# 6301_Lab3_ADC.net
KiCad netlist of a schematic drawn in Altium Designer
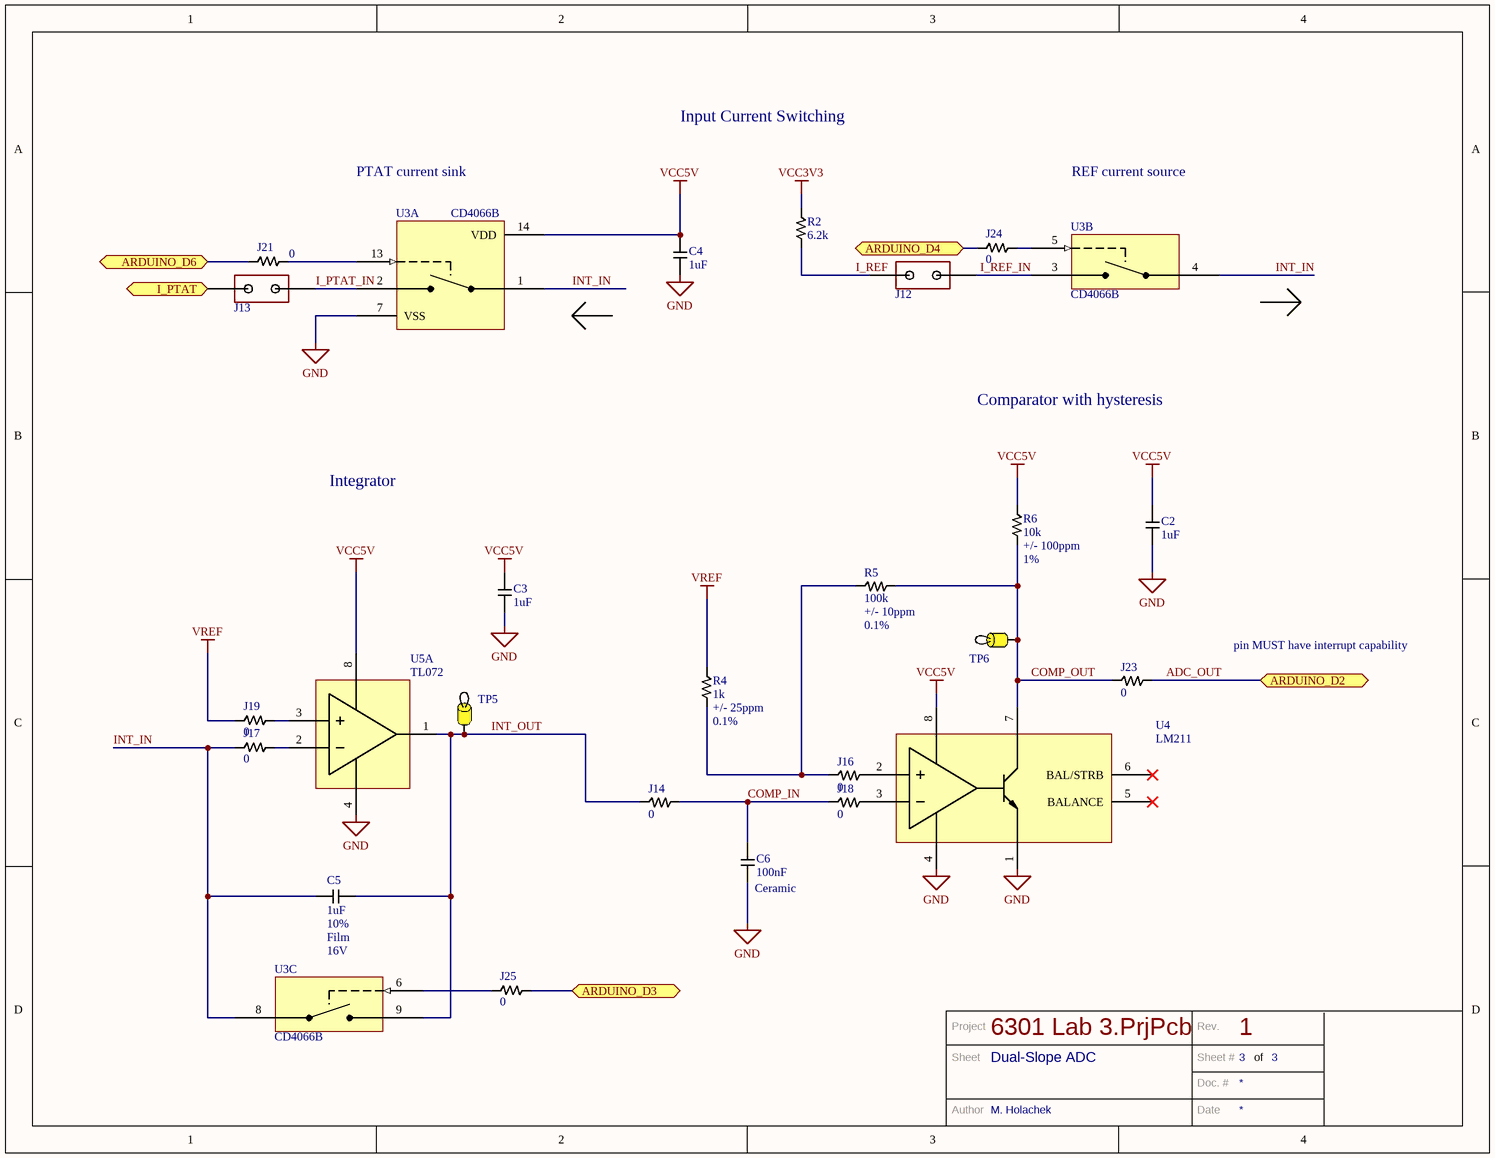
[diagram p0: 6301 Lab3 ADC.SchDoc]

(export (version "E")
  (design (tool "Eeschema 10.0.6"))
  (components
    (comp (ref "C2")
      (value "1uF")
      (footprint "CAP0805")
      (description "Capacitor, 0805 Package")
      (fields (field (name "TOLERANCE") "10%") (field (name "VOLTAGE") "25V"))
      (libsource (lib "6301 Lab 3") (part "Capacitor"))
    )
    (comp (ref "C3")
      (value "1uF")
      (footprint "CAP0805")
      (description "Capacitor, 0805 Package")
      (fields (field (name "TOLERANCE") "10%") (field (name "VOLTAGE") "25V"))
      (libsource (lib "6301 Lab 3") (part "Capacitor"))
    )
    (comp (ref "C4")
      (value "1uF")
      (footprint "CAP0805")
      (description "Capacitor, 0805 Package")
      (fields (field (name "TOLERANCE") "10%") (field (name "VOLTAGE") "25V"))
      (libsource (lib "6301 Lab 3") (part "Capacitor"))
    )
    (comp (ref "C5")
      (value "1uF")
      (footprint "CAP0805")
      (description "Capacitor, 0805 Package")
      (fields (field (name "TOLERANCE") "10%") (field (name "TYPE") "Film") (field (name "VOLTAGE") "16V"))
      (libsource (lib "6301 Lab 3") (part "Capacitor"))
    )
    (comp (ref "C6")
      (value "100nF")
      (footprint "CAP0805")
      (description "Capacitor, 0805 Package")
      (fields (field (name "TOLERANCE") "10%") (field (name "TYPE") "Ceramic") (field (name "VOLTAGE") "50V"))
      (libsource (lib "6301 Lab 3") (part "Capacitor"))
    )
    (comp (ref "J12")
      (value "Jumper")
      (footprint "1X02")
      (description "1x2 2.54mm Jumper")
      (libsource (lib "6301 Lab 3") (part "1x2"))
    )
    (comp (ref "J13")
      (value "Jumper")
      (footprint "1X02")
      (description "1x2 2.54mm Jumper")
      (libsource (lib "6301 Lab 3") (part "1x2"))
    )
    (comp (ref "J14")
      (value "0")
      (footprint "JUMP0402")
      (description "Jumper, 0402 Package")
      (libsource (lib "6301 Lab 3") (part "Jumper 0402"))
    )
    (comp (ref "J16")
      (value "0")
      (footprint "JUMP0402")
      (description "Jumper, 0402 Package")
      (libsource (lib "6301 Lab 3") (part "Jumper 0402"))
    )
    (comp (ref "J17")
      (value "0")
      (footprint "JUMP0402")
      (description "Jumper, 0402 Package")
      (libsource (lib "6301 Lab 3") (part "Jumper 0402"))
    )
    (comp (ref "J18")
      (value "0")
      (footprint "JUMP0402")
      (description "Jumper, 0402 Package")
      (libsource (lib "6301 Lab 3") (part "Jumper 0402"))
    )
    (comp (ref "J19")
      (value "0")
      (footprint "JUMP0402")
      (description "Jumper, 0402 Package")
      (libsource (lib "6301 Lab 3") (part "Jumper 0402"))
    )
    (comp (ref "J21")
      (value "0")
      (footprint "JUMP0402")
      (description "Jumper, 0402 Package")
      (libsource (lib "6301 Lab 3") (part "Jumper 0402"))
    )
    (comp (ref "J23")
      (value "0")
      (footprint "JUMP0402")
      (description "Jumper, 0402 Package")
      (libsource (lib "6301 Lab 3") (part "Jumper 0402"))
    )
    (comp (ref "J24")
      (value "0")
      (footprint "JUMP0402")
      (description "Jumper, 0402 Package")
      (libsource (lib "6301 Lab 3") (part "Jumper 0402"))
    )
    (comp (ref "J25")
      (value "0")
      (footprint "JUMP0402")
      (description "Jumper, 0402 Package")
      (libsource (lib "6301 Lab 3") (part "Jumper 0402"))
    )
    (comp (ref "R2")
      (value "6.2k")
      (footprint "RES0805")
      (description "Resistor, 0805 Package")
      (fields (field (name "TOLERANCE") "0.1%"))
      (libsource (lib "6301 Lab 3") (part "Resistor"))
    )
    (comp (ref "R4")
      (value "1k")
      (footprint "RES0805")
      (description "Resistor, 0805 Package")
      (fields (field (name "TEMP CO") "+/- 25ppm") (field (name "TOLERANCE") "0.1%"))
      (libsource (lib "6301 Lab 3") (part "Resistor"))
    )
    (comp (ref "R5")
      (value "100k")
      (footprint "RES0805")
      (description "Resistor, 0805 Package")
      (fields (field (name "TEMP CO") "+/- 10ppm") (field (name "TOLERANCE") "0.1%"))
      (libsource (lib "6301 Lab 3") (part "Resistor"))
    )
    (comp (ref "R6")
      (value "10k")
      (footprint "RES0805")
      (description "Resistor, 0805 Package")
      (fields (field (name "TEMP CO") "+/- 100ppm") (field (name "TOLERANCE") "1%"))
      (libsource (lib "6301 Lab 3") (part "Resistor"))
    )
    (comp (ref "TP5")
      (value "Yellow")
      (footprint "TP_YELLOW")
      (description "Yellow Test Point")
      (libsource (lib "") (part "Yellow Test Point_1"))
    )
    (comp (ref "TP6")
      (value "Yellow")
      (footprint "TP_YELLOW")
      (description "Yellow Test Point")
      (libsource (lib "6301 Lab 3") (part "Yellow Test Point"))
    )
    (comp (ref "U3")
      (value "CD4066B")
      (footprint "SOIC14")
      (description "CMOS Quad Bilateral Switch")
      (fields (field (name "MANUFACTURER") "Texas Instruments"))
      (libsource (lib "") (part "CD4066B_2"))
    )
    (comp (ref "U4")
      (value "LM211")
      (footprint "SOIC8")
      (description "Single Differential Comparator")
      (fields (field (name "MANUFACTURER") "Texas Instruments"))
      (libsource (lib "6301 Lab 3") (part "LMx11"))
    )
    (comp (ref "U5")
      (value "TL072")
      (footprint "SOIC8")
      (description "Dual Low-Noise JFET-Input Op Amp")
      (libsource (lib "6301 Lab 3") (part "TL07xx"))
    )
  )
  (nets
    (net (code "1") (name "/ADC_OUT") (class "Default")
      (node (ref "J23") (pin "1") (pinfunction "1_1") (pintype "passive"))
    )
    (net (code "2") (name "/ARDUINO_D3") (class "Default")
      (node (ref "J25") (pin "2") (pinfunction "2_2") (pintype "passive"))
    )
    (net (code "3") (name "/ARDUINO_D4") (class "Default")
      (node (ref "J24") (pin "1") (pinfunction "1_1") (pintype "passive"))
    )
    (net (code "4") (name "/ARDUINO_D6") (class "Default")
      (node (ref "J21") (pin "1") (pinfunction "1_1") (pintype "passive"))
    )
    (net (code "5") (name "/COMP_IN") (class "Default")
      (node (ref "C6") (pin "2") (pinfunction "2_2") (pintype "passive"))
      (node (ref "J14") (pin "1") (pinfunction "1_1") (pintype "passive"))
      (node (ref "J18") (pin "2") (pinfunction "2_2") (pintype "passive"))
    )
    (net (code "6") (name "/COMP_OUT") (class "Default")
      (node (ref "J23") (pin "2") (pinfunction "2_2") (pintype "passive"))
      (node (ref "R5") (pin "1") (pinfunction "1_1") (pintype "passive"))
      (node (ref "R6") (pin "1") (pinfunction "1_1") (pintype "passive"))
      (node (ref "TP6") (pin "1") (pinfunction "1_1") (pintype "passive"))
      (node (ref "U4") (pin "7") (pinfunction "COL_OUT_7") (pintype "passive"))
    )
    (net (code "7") (name "/INT_IN") (class "Default")
      (node (ref "C5") (pin "1") (pinfunction "1_1") (pintype "passive"))
      (node (ref "J17") (pin "1") (pinfunction "1_1") (pintype "passive"))
      (node (ref "U3") (pin "1") (pinfunction "IN_A_1") (pintype "passive"))
      (node (ref "U3") (pin "4") (pinfunction "IN_B_4") (pintype "passive"))
      (node (ref "U3") (pin "8") (pinfunction "IN_C_8") (pintype "passive"))
    )
    (net (code "8") (name "/INT_OUT") (class "Default")
      (node (ref "C5") (pin "2") (pinfunction "2_2") (pintype "passive"))
      (node (ref "J14") (pin "2") (pinfunction "2_2") (pintype "passive"))
      (node (ref "TP5") (pin "1") (pinfunction "1_1") (pintype "passive"))
      (node (ref "U3") (pin "9") (pinfunction "OUT_C_9") (pintype "passive"))
      (node (ref "U5") (pin "1") (pinfunction "1OUT_1") (pintype "passive"))
    )
    (net (code "9") (name "/I_PTAT") (class "Default")
      (node (ref "J13") (pin "2") (pinfunction "2_2") (pintype "passive"))
    )
    (net (code "10") (name "/I_PTAT_IN") (class "Default")
      (node (ref "J13") (pin "1") (pinfunction "1_1") (pintype "passive"))
      (node (ref "U3") (pin "2") (pinfunction "OUT_A_2") (pintype "passive"))
    )
    (net (code "11") (name "/I_REF") (class "Default")
      (node (ref "J12") (pin "2") (pinfunction "2_2") (pintype "passive"))
      (node (ref "R2") (pin "1") (pinfunction "1_1") (pintype "passive"))
    )
    (net (code "12") (name "/I_REF_IN") (class "Default")
      (node (ref "J12") (pin "1") (pinfunction "1_1") (pintype "passive"))
      (node (ref "U3") (pin "3") (pinfunction "OUT_B_3") (pintype "passive"))
    )
    (net (code "13") (name "GND") (class "Default")
      (node (ref "C2") (pin "1") (pinfunction "1_1") (pintype "passive"))
      (node (ref "C3") (pin "1") (pinfunction "1_1") (pintype "passive"))
      (node (ref "C4") (pin "1") (pinfunction "1_1") (pintype "passive"))
      (node (ref "C6") (pin "1") (pinfunction "1_1") (pintype "passive"))
      (node (ref "U3") (pin "7") (pinfunction "VSS_7") (pintype "power_in"))
      (node (ref "U4") (pin "1") (pinfunction "EMIT_OUT_1") (pintype "passive"))
      (node (ref "U4") (pin "4") (pinfunction "VCC-_4") (pintype "passive"))
      (node (ref "U5") (pin "4") (pinfunction "VCC-_4") (pintype "passive"))
    )
    (net (code "14") (name "Net-(J16-Pad2)") (class "Default")
      (node (ref "J16") (pin "2") (pinfunction "2_2") (pintype "passive"))
      (node (ref "R4") (pin "1") (pinfunction "1_1") (pintype "passive"))
      (node (ref "R5") (pin "2") (pinfunction "2_2") (pintype "passive"))
    )
    (net (code "15") (name "Net-(U3A-EN_A)") (class "Default")
      (node (ref "J21") (pin "2") (pinfunction "2_2") (pintype "passive"))
      (node (ref "U3") (pin "13") (pinfunction "EN_A_13") (pintype "input"))
    )
    (net (code "16") (name "Net-(U3B-EN_B)") (class "Default")
      (node (ref "J24") (pin "2") (pinfunction "2_2") (pintype "passive"))
      (node (ref "U3") (pin "5") (pinfunction "EN_B_5") (pintype "input"))
    )
    (net (code "17") (name "Net-(U3C-EN_C)") (class "Default")
      (node (ref "J25") (pin "1") (pinfunction "1_1") (pintype "passive"))
      (node (ref "U3") (pin "6") (pinfunction "EN_C_6") (pintype "input"))
    )
    (net (code "18") (name "Net-(U4-IN+)") (class "Default")
      (node (ref "J16") (pin "1") (pinfunction "1_1") (pintype "passive"))
      (node (ref "U4") (pin "2") (pinfunction "IN+_2") (pintype "passive"))
    )
    (net (code "19") (name "Net-(U4-IN-)") (class "Default")
      (node (ref "J18") (pin "1") (pinfunction "1_1") (pintype "passive"))
      (node (ref "U4") (pin "3") (pinfunction "IN-_3") (pintype "passive"))
    )
    (net (code "20") (name "Net-(U5A-1IN+)") (class "Default")
      (node (ref "J19") (pin "2") (pinfunction "2_2") (pintype "passive"))
      (node (ref "U5") (pin "3") (pinfunction "1IN+_3") (pintype "passive"))
    )
    (net (code "21") (name "Net-(U5A-1IN-)") (class "Default")
      (node (ref "J17") (pin "2") (pinfunction "2_2") (pintype "passive"))
      (node (ref "U5") (pin "2") (pinfunction "1IN-_2") (pintype "passive"))
    )
    (net (code "22") (name "VCC3V3") (class "Default")
      (node (ref "R2") (pin "2") (pinfunction "2_2") (pintype "passive"))
    )
    (net (code "23") (name "VCC5V") (class "Default")
      (node (ref "C2") (pin "2") (pinfunction "2_2") (pintype "passive"))
      (node (ref "C3") (pin "2") (pinfunction "2_2") (pintype "passive"))
      (node (ref "C4") (pin "2") (pinfunction "2_2") (pintype "passive"))
      (node (ref "R6") (pin "2") (pinfunction "2_2") (pintype "passive"))
      (node (ref "U3") (pin "14") (pinfunction "VDD_14") (pintype "power_in"))
      (node (ref "U4") (pin "8") (pinfunction "VCC+_8") (pintype "passive"))
      (node (ref "U5") (pin "8") (pinfunction "VCC+_8") (pintype "passive"))
    )
    (net (code "24") (name "VREF") (class "Default")
      (node (ref "J19") (pin "1") (pinfunction "1_1") (pintype "passive"))
      (node (ref "R4") (pin "2") (pinfunction "2_2") (pintype "passive"))
    )
    (net (code "25") (name "unconnected-(U4-BALANCE-Pad5)") (class "Default")
      (node (ref "U4") (pin "5") (pinfunction "BALANCE_5") (pintype "passive+no_connect"))
    )
    (net (code "26") (name "unconnected-(U4-BAL{slash}STRB-Pad6)") (class "Default")
      (node (ref "U4") (pin "6") (pinfunction "BAL/STRB_6") (pintype "passive+no_connect"))
    )
  )
)
